# 11_-_Power_Input_and_Regulators.net
KiCad netlist of a schematic drawn in Altium Designer
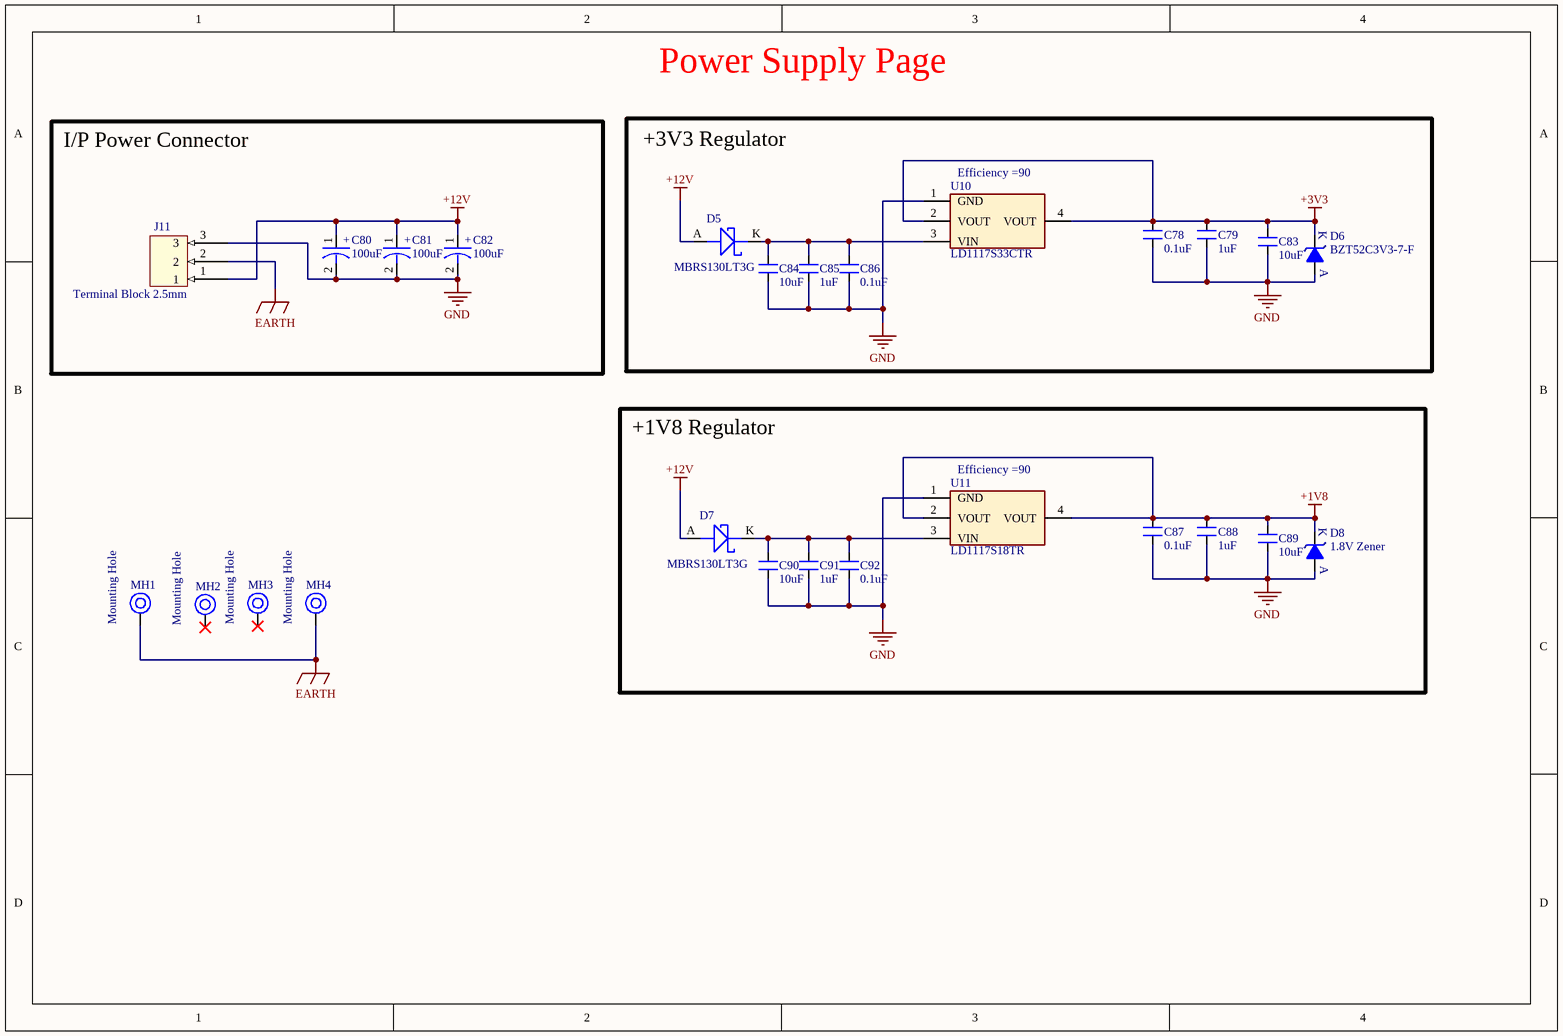
[diagram p0: [11]- Power Input and Regulators.SchDoc]

(export (version "E")
  (design (tool "Eeschema 10.0.6"))
  (components
    (comp (ref "C78")
      (value "0.1uF")
      (footprint "CAP_0805")
      (description "0.1µF ±10% 50V Ceramic Capacitor X7R 0805 (2012 Metric)")
      (fields
        (field (name "MANUFACTURER") "Samsung")
        (field (name "MANUFACTURER PART NUMBER") "CL21B104KBCNNNC")
      )
      (libsource (lib "ESTEEMPCBLIB") (part "CAP_0.1uF-50V-10%-0805"))
    )
    (comp (ref "C79")
      (value "1uF")
      (footprint "CAP_0805")
      (description "1µF ±5% 50V Ceramic Capacitor X7R 0805 (2012 Metric)")
      (fields
        (field (name "MANUFACTURER") "Samsung")
        (field (name "MANUFACTURER PART NUMBER") "CC0805JKX7R9BB105")
      )
      (libsource (lib "ESTEEMPCBLIB") (part "CAP_1uF-50V-5%-0805"))
    )
    (comp (ref "C80")
      (value "100uF")
      (footprint "ACAP_P305_D393_H393_RAD")
      (description "100µF 50V Aluminum Polymer Capacitor Radial, Can - SMD 28mOhm 4000 Hrs @ 125°C")
      (fields
        (field (name "MANUFACTURER") "Nichicon")
        (field (name "MANUFACTURER PART NUMBER") "GYA1H101MCQ1GS")
      )
      (libsource (lib "ESTEEMPCBLIB") (part "CAP-P_100uF-50V-20%-RAD"))
    )
    (comp (ref "C81")
      (value "100uF")
      (footprint "ACAP_P305_D393_H393_RAD")
      (description "100µF 50V Aluminum Polymer Capacitor Radial, Can - SMD 28mOhm 4000 Hrs @ 125°C")
      (fields
        (field (name "MANUFACTURER") "Nichicon")
        (field (name "MANUFACTURER PART NUMBER") "GYA1H101MCQ1GS")
      )
      (libsource (lib "ESTEEMPCBLIB") (part "CAP-P_100uF-50V-20%-RAD"))
    )
    (comp (ref "C82")
      (value "100uF")
      (footprint "ACAP_P305_D393_H393_RAD")
      (description "100µF 50V Aluminum Polymer Capacitor Radial, Can - SMD 28mOhm 4000 Hrs @ 125°C")
      (fields
        (field (name "MANUFACTURER") "Nichicon")
        (field (name "MANUFACTURER PART NUMBER") "GYA1H101MCQ1GS")
      )
      (libsource (lib "ESTEEMPCBLIB") (part "CAP-P_100uF-50V-20%-RAD"))
    )
    (comp (ref "C83")
      (value "10uF")
      (footprint "CAP_1206")
      (description "10µF ±10% 50V Ceramic Capacitor X7R 1206 (3216 Metric)")
      (fields
        (field (name "MANUFACTURER") "KEMET")
        (field (name "MANUFACTURER PART NUMBER") "CL31B106KBHNNNE")
      )
      (libsource (lib "ESTEEMPCBLIB") (part "CAP_10uF-50V-10%-1206"))
    )
    (comp (ref "C84")
      (value "10uF")
      (footprint "CAP_1206")
      (description "10µF ±10% 50V Ceramic Capacitor X7R 1206 (3216 Metric)")
      (fields
        (field (name "MANUFACTURER") "KEMET")
        (field (name "MANUFACTURER PART NUMBER") "CL31B106KBHNNNE")
      )
      (libsource (lib "ESTEEMPCBLIB") (part "CAP_10uF-50V-10%-1206"))
    )
    (comp (ref "C85")
      (value "1uF")
      (footprint "CAP_0805")
      (description "1µF ±5% 50V Ceramic Capacitor X7R 0805 (2012 Metric)")
      (fields
        (field (name "MANUFACTURER") "Samsung")
        (field (name "MANUFACTURER PART NUMBER") "CC0805JKX7R9BB105")
      )
      (libsource (lib "ESTEEMPCBLIB") (part "CAP_1uF-50V-5%-0805"))
    )
    (comp (ref "C86")
      (value "0.1uF")
      (footprint "CAP_0805")
      (description "0.1µF ±10% 50V Ceramic Capacitor X7R 0805 (2012 Metric)")
      (fields
        (field (name "MANUFACTURER") "Samsung")
        (field (name "MANUFACTURER PART NUMBER") "CL21B104KBCNNNC")
      )
      (libsource (lib "ESTEEMPCBLIB") (part "CAP_0.1uF-50V-10%-0805"))
    )
    (comp (ref "C87")
      (value "0.1uF")
      (footprint "CAP_0805")
      (description "0.1µF ±10% 50V Ceramic Capacitor X7R 0805 (2012 Metric)")
      (fields
        (field (name "MANUFACTURER") "Samsung")
        (field (name "MANUFACTURER PART NUMBER") "CL21B104KBCNNNC")
      )
      (libsource (lib "ESTEEMPCBLIB") (part "CAP_0.1uF-50V-10%-0805"))
    )
    (comp (ref "C88")
      (value "1uF")
      (footprint "CAP_0805")
      (description "1µF ±5% 50V Ceramic Capacitor X7R 0805 (2012 Metric)")
      (fields
        (field (name "MANUFACTURER") "Samsung")
        (field (name "MANUFACTURER PART NUMBER") "CC0805JKX7R9BB105")
      )
      (libsource (lib "ESTEEMPCBLIB") (part "CAP_1uF-50V-5%-0805"))
    )
    (comp (ref "C89")
      (value "10uF")
      (footprint "CAP_1206")
      (description "10µF ±10% 50V Ceramic Capacitor X7R 1206 (3216 Metric)")
      (fields
        (field (name "MANUFACTURER") "KEMET")
        (field (name "MANUFACTURER PART NUMBER") "CL31B106KBHNNNE")
      )
      (libsource (lib "ESTEEMPCBLIB") (part "CAP_10uF-50V-10%-1206"))
    )
    (comp (ref "C90")
      (value "10uF")
      (footprint "CAP_1206")
      (description "10µF ±10% 50V Ceramic Capacitor X7R 1206 (3216 Metric)")
      (fields
        (field (name "MANUFACTURER") "KEMET")
        (field (name "MANUFACTURER PART NUMBER") "CL31B106KBHNNNE")
      )
      (libsource (lib "ESTEEMPCBLIB") (part "CAP_10uF-50V-10%-1206"))
    )
    (comp (ref "C91")
      (value "1uF")
      (footprint "CAP_0805")
      (description "1µF ±5% 50V Ceramic Capacitor X7R 0805 (2012 Metric)")
      (fields
        (field (name "MANUFACTURER") "Samsung")
        (field (name "MANUFACTURER PART NUMBER") "CC0805JKX7R9BB105")
      )
      (libsource (lib "ESTEEMPCBLIB") (part "CAP_1uF-50V-5%-0805"))
    )
    (comp (ref "C92")
      (value "0.1uF")
      (footprint "CAP_0805")
      (description "0.1µF ±10% 50V Ceramic Capacitor X7R 0805 (2012 Metric)")
      (fields
        (field (name "MANUFACTURER") "Samsung")
        (field (name "MANUFACTURER PART NUMBER") "CL21B104KBCNNNC")
      )
      (libsource (lib "ESTEEMPCBLIB") (part "CAP_0.1uF-50V-10%-0805"))
    )
    (comp (ref "D5")
      (value "MBRS130LT3G")
      (footprint "DIO_SMB_DO-214AA")
      (description "Diode Schottky 30V 2A Surface Mount SMB")
      (fields (field (name "MANUFACTURER") "ON Semiconductor"))
      (libsource (lib "ESTEEMPCBLIB") (part "DIO-S_445mV-30V-2A-SMB"))
    )
    (comp (ref "D6")
      (value "BZT52C3V3-7-F")
      (footprint "DIO_SOD-123")
      (description "Zener Diode 3.3V 500mW ±6% Surface Mount SOD-123")
      (fields (field (name "MANUFACTURER") "Diodes Incorporated"))
      (libsource (lib "ESTEEMPCBLIB") (part "DIO-Z_3.3V-500mW-SOD123"))
    )
    (comp (ref "D7")
      (value "MBRS130LT3G")
      (footprint "DIO_SMB_DO-214AA")
      (description "Diode Schottky 30V 2A Surface Mount SMB")
      (fields (field (name "MANUFACTURER") "ON Semiconductor"))
      (libsource (lib "ESTEEMPCBLIB") (part "DIO-S_445mV-30V-2A-SMB"))
    )
    (comp (ref "D8")
      (value "1.8V Zener")
      (footprint "DIO_DO-213AB_SMD")
      (description "Zener Diode 1.8V 500mW ±5% Surface Mount DO-213AA")
      (libsource (lib "ESTEEMPCBLIB") (part "DIO-Z_1.8V-500mW-DO213AA"))
    )
    (comp (ref "J11")
      (value "Terminal Block 2.5mm")
      (footprint "CON3_100_TB_TH_ST")
      (description "3 Pins, 1 Row 2.54mm Pitch, straight Connector, male")
      (fields
        (field (name "MANUFACTURER PART NUMBER") "1725669")
        (field (name "MANUFACTURER") "Phoenix Contact")
      )
      (libsource (lib "ESTEEMPCBLIB") (part "CON-TB_3X1-100-ST-TH"))
    )
    (comp (ref "MH1")
      (value "Mounting Hole")
      (footprint "MOUNTING")
      (fields (field (name "MANUFACTURER PART NUMBER") "NA"))
      (libsource (lib "ESTEEMPCBLIB") (part "MH_3.5H_6D"))
    )
    (comp (ref "MH2")
      (value "Mounting Hole")
      (footprint "MOUNTING")
      (fields (field (name "MANUFACTURER PART NUMBER") "NA"))
      (libsource (lib "ESTEEMPCBLIB") (part "MH_3.5H_6D"))
    )
    (comp (ref "MH3")
      (value "Mounting Hole")
      (footprint "MOUNTING")
      (fields (field (name "MANUFACTURER PART NUMBER") "NA"))
      (libsource (lib "ESTEEMPCBLIB") (part "MH_3.5H_6D"))
    )
    (comp (ref "MH4")
      (value "Mounting Hole")
      (footprint "MOUNTING")
      (fields (field (name "MANUFACTURER PART NUMBER") "NA"))
      (libsource (lib "ESTEEMPCBLIB") (part "MH_3.5H_6D"))
    )
    (comp (ref "U10")
      (value "LD1117S33CTR")
      (footprint "SOT223_3")
      (description "Linear Voltage Regulator IC 1 Output 800mA SOT-223")
      (fields (field (name "MANUFACTURER") "STMicroelectronics"))
      (libsource (lib "ESTEEMPCBLIB") (part "REG_15V-3.3V-0.9A-12W-SOT223"))
    )
    (comp (ref "U11")
      (value "LD1117S18TR")
      (footprint "SOT223_3")
      (description "LDO Voltage Regulators 1.8V 0.8A Positive")
      (fields (field (name "MANUFACTURER") "STMicroelectronics"))
      (libsource (lib "ESTEEMPCBLIB") (part "REG_15V-1.8V-0.8A-1.4W-SOT223"))
    )
  )
  (nets
    (net (code "1") (name "+1V8") (class "Default")
      (node (ref "C87") (pin "2") (pinfunction "2_2") (pintype "passive"))
      (node (ref "C88") (pin "2") (pinfunction "2_2") (pintype "passive"))
      (node (ref "C89") (pin "2") (pinfunction "2_2") (pintype "passive"))
      (node (ref "D8") (pin "K") (pinfunction "K_K") (pintype "passive"))
      (node (ref "U11") (pin "2") (pinfunction "VOUT_2") (pintype "passive"))
      (node (ref "U11") (pin "4") (pinfunction "VOUT_4") (pintype "passive"))
    )
    (net (code "2") (name "+3V3") (class "Default")
      (node (ref "C78") (pin "2") (pinfunction "2_2") (pintype "passive"))
      (node (ref "C79") (pin "2") (pinfunction "2_2") (pintype "passive"))
      (node (ref "C83") (pin "2") (pinfunction "2_2") (pintype "passive"))
      (node (ref "D6") (pin "K") (pinfunction "K_K") (pintype "passive"))
      (node (ref "U10") (pin "2") (pinfunction "VOUT_2") (pintype "passive"))
      (node (ref "U10") (pin "4") (pinfunction "VOUT_4") (pintype "passive"))
    )
    (net (code "3") (name "+12V") (class "Default")
      (node (ref "C80") (pin "1") (pinfunction "1_1") (pintype "passive"))
      (node (ref "C81") (pin "1") (pinfunction "1_1") (pintype "passive"))
      (node (ref "C82") (pin "1") (pinfunction "1_1") (pintype "passive"))
      (node (ref "D5") (pin "A") (pinfunction "A_A") (pintype "passive"))
      (node (ref "D7") (pin "A") (pinfunction "A_A") (pintype "passive"))
      (node (ref "J11") (pin "1") (pinfunction "1_1") (pintype "input"))
    )
    (net (code "4") (name "EARTH") (class "Default")
      (node (ref "J11") (pin "2") (pinfunction "2_2") (pintype "input"))
      (node (ref "MH1") (pin "1") (pinfunction "1_1") (pintype "passive"))
      (node (ref "MH4") (pin "1") (pinfunction "1_1") (pintype "passive"))
    )
    (net (code "5") (name "GND") (class "Default")
      (node (ref "C78") (pin "1") (pinfunction "1_1") (pintype "passive"))
      (node (ref "C79") (pin "1") (pinfunction "1_1") (pintype "passive"))
      (node (ref "C80") (pin "2") (pinfunction "2_2") (pintype "passive"))
      (node (ref "C81") (pin "2") (pinfunction "2_2") (pintype "passive"))
      (node (ref "C82") (pin "2") (pinfunction "2_2") (pintype "passive"))
      (node (ref "C83") (pin "1") (pinfunction "1_1") (pintype "passive"))
      (node (ref "C84") (pin "1") (pinfunction "1_1") (pintype "passive"))
      (node (ref "C85") (pin "1") (pinfunction "1_1") (pintype "passive"))
      (node (ref "C86") (pin "1") (pinfunction "1_1") (pintype "passive"))
      (node (ref "C87") (pin "1") (pinfunction "1_1") (pintype "passive"))
      (node (ref "C88") (pin "1") (pinfunction "1_1") (pintype "passive"))
      (node (ref "C89") (pin "1") (pinfunction "1_1") (pintype "passive"))
      (node (ref "C90") (pin "1") (pinfunction "1_1") (pintype "passive"))
      (node (ref "C91") (pin "1") (pinfunction "1_1") (pintype "passive"))
      (node (ref "C92") (pin "1") (pinfunction "1_1") (pintype "passive"))
      (node (ref "D6") (pin "A") (pinfunction "A_A") (pintype "passive"))
      (node (ref "D8") (pin "A") (pinfunction "A_A") (pintype "passive"))
      (node (ref "J11") (pin "3") (pinfunction "3_3") (pintype "input"))
      (node (ref "U10") (pin "1") (pinfunction "GND_1") (pintype "passive"))
      (node (ref "U11") (pin "1") (pinfunction "GND_1") (pintype "passive"))
    )
    (net (code "6") (name "Net-(U10-VIN)") (class "Default")
      (node (ref "C84") (pin "2") (pinfunction "2_2") (pintype "passive"))
      (node (ref "C85") (pin "2") (pinfunction "2_2") (pintype "passive"))
      (node (ref "C86") (pin "2") (pinfunction "2_2") (pintype "passive"))
      (node (ref "D5") (pin "K") (pinfunction "K_K") (pintype "passive"))
      (node (ref "U10") (pin "3") (pinfunction "VIN_3") (pintype "passive"))
    )
    (net (code "7") (name "Net-(U11-VIN)") (class "Default")
      (node (ref "C90") (pin "2") (pinfunction "2_2") (pintype "passive"))
      (node (ref "C91") (pin "2") (pinfunction "2_2") (pintype "passive"))
      (node (ref "C92") (pin "2") (pinfunction "2_2") (pintype "passive"))
      (node (ref "D7") (pin "K") (pinfunction "K_K") (pintype "passive"))
      (node (ref "U11") (pin "3") (pinfunction "VIN_3") (pintype "passive"))
    )
    (net (code "8") (name "unconnected-(MH2-Pad1)") (class "Default")
      (node (ref "MH2") (pin "1") (pinfunction "1_1") (pintype "passive+no_connect"))
    )
    (net (code "9") (name "unconnected-(MH3-Pad1)") (class "Default")
      (node (ref "MH3") (pin "1") (pinfunction "1_1") (pintype "passive+no_connect"))
    )
  )
)
